# Bridge.net
KiCad netlist of a schematic drawn in Altium Designer
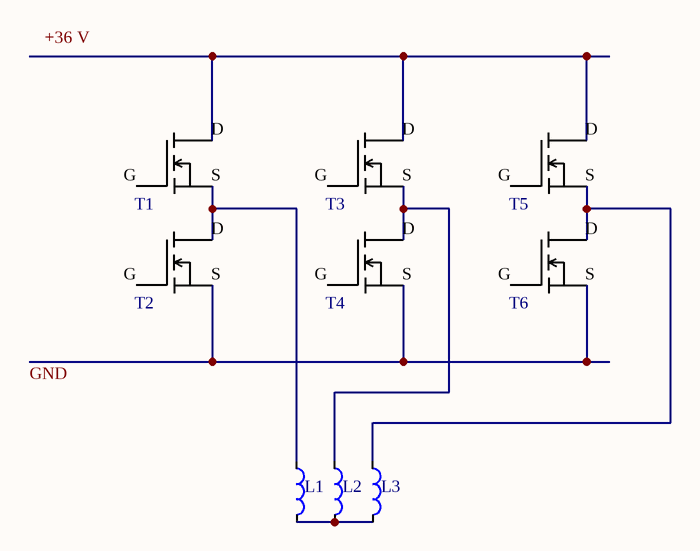
[diagram p0: Bridge.SchDoc]

(export (version "E")
  (design (tool "Eeschema 10.0.6"))
  (components
    (comp (ref "L1") (value "Inductance") (libsource (lib "GOST_UGO") (part "Inductance")))
    (comp (ref "L2") (value "Inductance") (libsource (lib "GOST_UGO") (part "Inductance")))
    (comp (ref "L3") (value "Inductance") (libsource (lib "GOST_UGO") (part "Inductance")))
    (comp (ref "T1")
      (value "MOSFET_Isolated_Gate")
      (libsource (lib "GOST_UGO") (part "MOSFET_Isolated_Gate"))
    )
    (comp (ref "T2")
      (value "MOSFET_Isolated_Gate")
      (libsource (lib "GOST_UGO") (part "MOSFET_Isolated_Gate"))
    )
    (comp (ref "T3")
      (value "MOSFET_Isolated_Gate")
      (libsource (lib "GOST_UGO") (part "MOSFET_Isolated_Gate"))
    )
    (comp (ref "T4")
      (value "MOSFET_Isolated_Gate")
      (libsource (lib "GOST_UGO") (part "MOSFET_Isolated_Gate"))
    )
    (comp (ref "T5")
      (value "MOSFET_Isolated_Gate")
      (libsource (lib "GOST_UGO") (part "MOSFET_Isolated_Gate"))
    )
    (comp (ref "T6")
      (value "MOSFET_Isolated_Gate")
      (libsource (lib "GOST_UGO") (part "MOSFET_Isolated_Gate"))
    )
  )
  (nets
    (net (code "3") (name "Net-(L1-Pad1)") (class "Default")
      (node (ref "L1") (pin "1") (pinfunction "1_1") (pintype "passive"))
      (node (ref "T1") (pin "S") (pinfunction "S_S") (pintype "passive"))
      (node (ref "T2") (pin "D") (pinfunction "D_D") (pintype "passive"))
    )
    (net (code "4") (name "Net-(L1-Pad2)") (class "Default")
      (node (ref "L1") (pin "2") (pinfunction "2_2") (pintype "passive"))
      (node (ref "L2") (pin "2") (pinfunction "2_2") (pintype "passive"))
      (node (ref "L3") (pin "2") (pinfunction "2_2") (pintype "passive"))
    )
    (net (code "5") (name "Net-(L2-Pad1)") (class "Default")
      (node (ref "L2") (pin "1") (pinfunction "1_1") (pintype "passive"))
      (node (ref "T3") (pin "S") (pinfunction "S_S") (pintype "passive"))
      (node (ref "T4") (pin "D") (pinfunction "D_D") (pintype "passive"))
    )
    (net (code "6") (name "Net-(L3-Pad1)") (class "Default")
      (node (ref "L3") (pin "1") (pinfunction "1_1") (pintype "passive"))
      (node (ref "T5") (pin "S") (pinfunction "S_S") (pintype "passive"))
      (node (ref "T6") (pin "D") (pinfunction "D_D") (pintype "passive"))
    )
    (net (code "7") (name "Net-(T1-PadD)") (class "Default")
      (node (ref "T1") (pin "D") (pinfunction "D_D") (pintype "passive"))
      (node (ref "T3") (pin "D") (pinfunction "D_D") (pintype "passive"))
      (node (ref "T5") (pin "D") (pinfunction "D_D") (pintype "passive"))
    )
    (net (code "8") (name "Net-(T2-PadS)") (class "Default")
      (node (ref "T2") (pin "S") (pinfunction "S_S") (pintype "passive"))
      (node (ref "T4") (pin "S") (pinfunction "S_S") (pintype "passive"))
      (node (ref "T6") (pin "S") (pinfunction "S_S") (pintype "passive"))
    )
    (net (code "9") (name "unconnected-(T1-1-PadG)") (class "Default")
      (node (ref "T1") (pin "G") (pinfunction "1_G") (pintype "passive"))
    )
    (net (code "10") (name "unconnected-(T2-1-PadG)") (class "Default")
      (node (ref "T2") (pin "G") (pinfunction "1_G") (pintype "passive"))
    )
    (net (code "11") (name "unconnected-(T3-1-PadG)") (class "Default")
      (node (ref "T3") (pin "G") (pinfunction "1_G") (pintype "passive"))
    )
    (net (code "12") (name "unconnected-(T4-1-PadG)") (class "Default")
      (node (ref "T4") (pin "G") (pinfunction "1_G") (pintype "passive"))
    )
    (net (code "13") (name "unconnected-(T5-1-PadG)") (class "Default")
      (node (ref "T5") (pin "G") (pinfunction "1_G") (pintype "passive"))
    )
    (net (code "14") (name "unconnected-(T6-1-PadG)") (class "Default")
      (node (ref "T6") (pin "G") (pinfunction "1_G") (pintype "passive"))
    )
  )
)
